# con-left-bot.net
KiCad netlist of a schematic drawn in Altium Designer
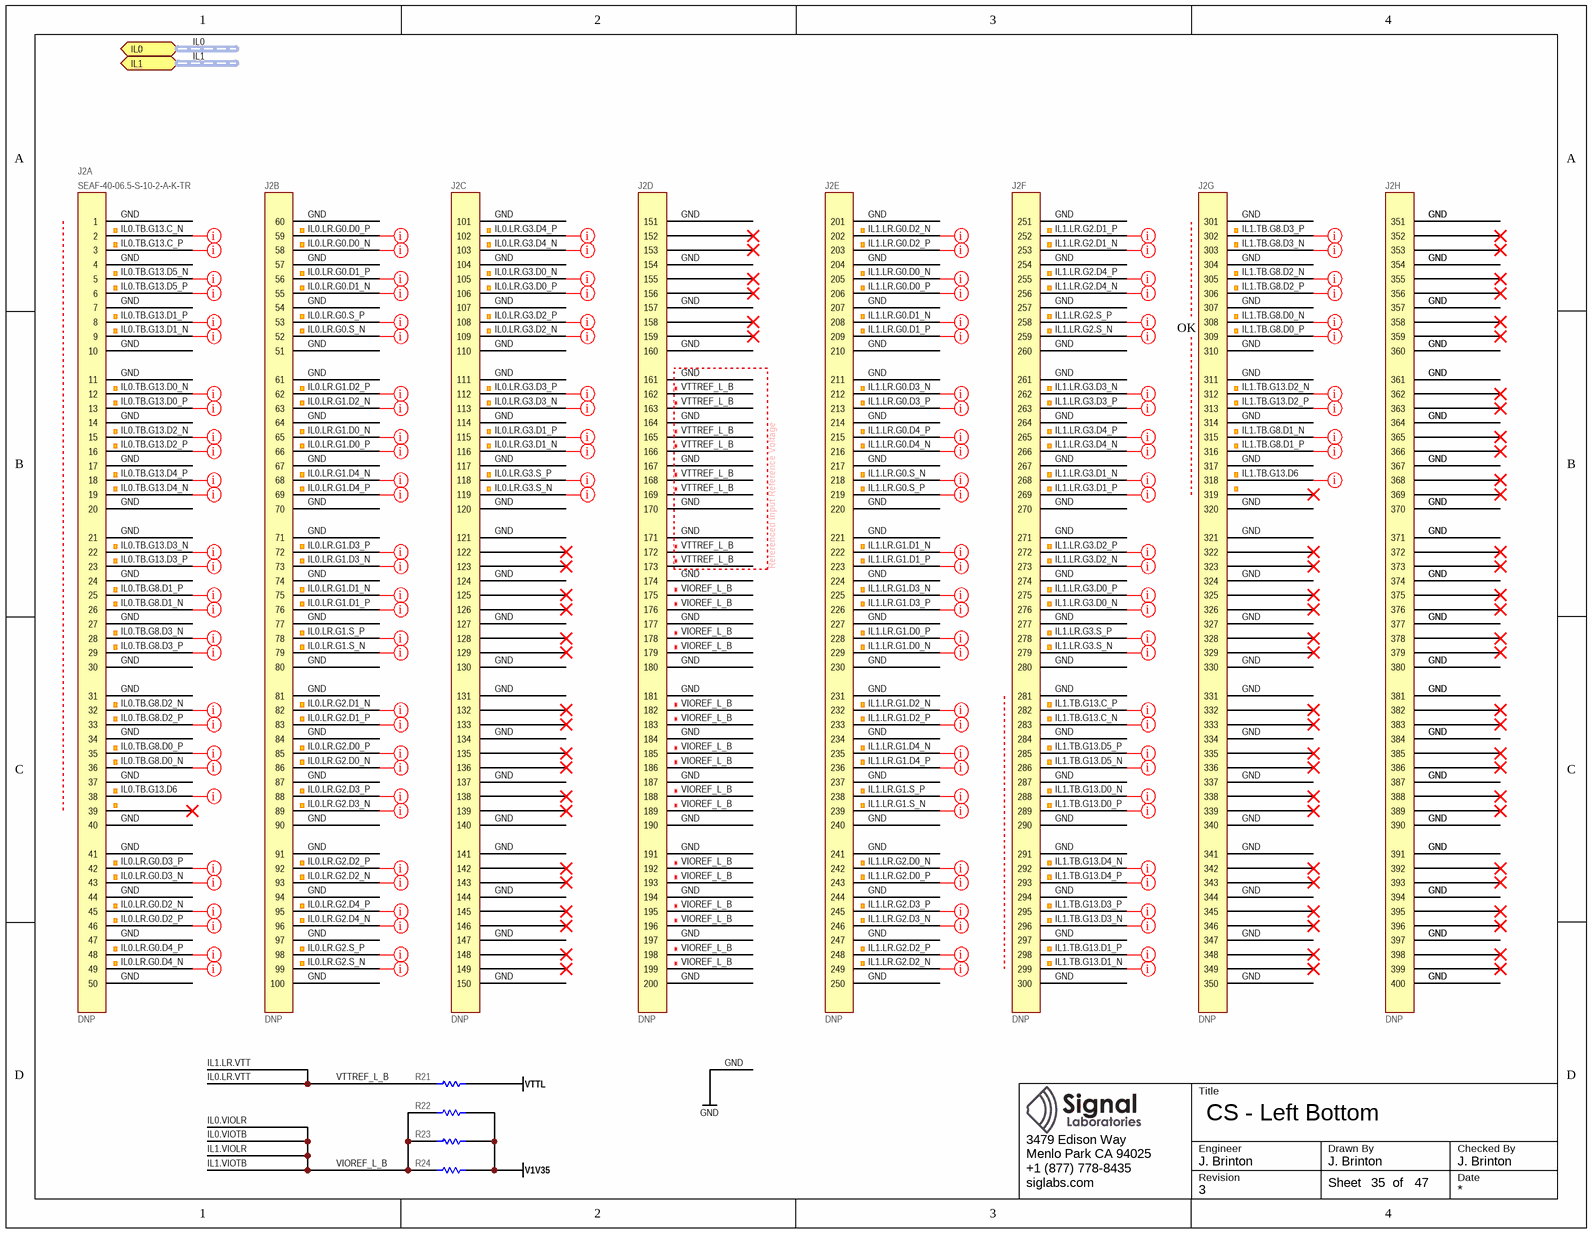
[diagram p0: con-left-bot.SchDoc]

(export (version "E")
  (design (tool "Eeschema 10.0.6"))
  (components
    (comp (ref "J2")
      (value "SEAF-40-06.5-S-10-2-A-K-TR")
      (footprint "samtec:SEAF-40-06.5-S-10-2-A-K-TR")
      (description "Terminal Array Assembly, Surface Mount, 0.050\" Pitch, 400 Pins")
      (fields (field (name "MANUFACTURER") "Samtec") (field (name "DO NOT PLACE") "DNP"))
      (libsource (lib "samtec") (part "SEAF-40-06.5-S-10-2-A-K-TR"))
    )
    (comp (ref "R21")
      (value "SOLDER_LINK")
      (footprint "SOLDERLINK0603X26N")
      (description "Solder Link")
      (libsource (lib "generic") (part "RES"))
    )
    (comp (ref "R22")
      (value "SOLDER_LINK")
      (footprint "SOLDERLINK0603X26N")
      (description "Solder Link")
      (libsource (lib "generic") (part "RES"))
    )
    (comp (ref "R23")
      (value "SOLDER_LINK")
      (footprint "SOLDERLINK0603X26N")
      (description "Solder Link")
      (libsource (lib "generic") (part "RES"))
    )
    (comp (ref "R24")
      (value "SOLDER_LINK")
      (footprint "SOLDERLINK0603X26N")
      (description "Solder Link")
      (libsource (lib "generic") (part "RES"))
    )
  )
  (nets
    (net (code "3") (name "/IL0.LR.G0.D0_N") (class "Default")
      (node (ref "J2") (pin "58") (pinfunction "58_58") (pintype "passive"))
    )
    (net (code "4") (name "/IL0.LR.G0.D0_P") (class "Default")
      (node (ref "J2") (pin "59") (pinfunction "59_59") (pintype "passive"))
    )
    (net (code "5") (name "/IL0.LR.G0.D1_N") (class "Default")
      (node (ref "J2") (pin "55") (pinfunction "55_55") (pintype "passive"))
    )
    (net (code "6") (name "/IL0.LR.G0.D1_P") (class "Default")
      (node (ref "J2") (pin "56") (pinfunction "56_56") (pintype "passive"))
    )
    (net (code "7") (name "/IL0.LR.G0.D2_N") (class "Default")
      (node (ref "J2") (pin "45") (pinfunction "45_45") (pintype "passive"))
    )
    (net (code "8") (name "/IL0.LR.G0.D2_P") (class "Default")
      (node (ref "J2") (pin "46") (pinfunction "46_46") (pintype "passive"))
    )
    (net (code "9") (name "/IL0.LR.G0.D3_N") (class "Default")
      (node (ref "J2") (pin "43") (pinfunction "43_43") (pintype "passive"))
    )
    (net (code "10") (name "/IL0.LR.G0.D3_P") (class "Default")
      (node (ref "J2") (pin "42") (pinfunction "42_42") (pintype "passive"))
    )
    (net (code "11") (name "/IL0.LR.G0.D4_N") (class "Default")
      (node (ref "J2") (pin "49") (pinfunction "49_49") (pintype "passive"))
    )
    (net (code "12") (name "/IL0.LR.G0.D4_P") (class "Default")
      (node (ref "J2") (pin "48") (pinfunction "48_48") (pintype "passive"))
    )
    (net (code "13") (name "/IL0.LR.G0.S_N") (class "Default")
      (node (ref "J2") (pin "52") (pinfunction "52_52") (pintype "passive"))
    )
    (net (code "14") (name "/IL0.LR.G0.S_P") (class "Default")
      (node (ref "J2") (pin "53") (pinfunction "53_53") (pintype "passive"))
    )
    (net (code "15") (name "/IL0.LR.G1.D0_N") (class "Default")
      (node (ref "J2") (pin "65") (pinfunction "65_65") (pintype "passive"))
    )
    (net (code "16") (name "/IL0.LR.G1.D0_P") (class "Default")
      (node (ref "J2") (pin "66") (pinfunction "66_66") (pintype "passive"))
    )
    (net (code "17") (name "/IL0.LR.G1.D1_N") (class "Default")
      (node (ref "J2") (pin "75") (pinfunction "75_75") (pintype "passive"))
    )
    (net (code "18") (name "/IL0.LR.G1.D1_P") (class "Default")
      (node (ref "J2") (pin "76") (pinfunction "76_76") (pintype "passive"))
    )
    (net (code "19") (name "/IL0.LR.G1.D2_N") (class "Default")
      (node (ref "J2") (pin "63") (pinfunction "63_63") (pintype "passive"))
    )
    (net (code "20") (name "/IL0.LR.G1.D2_P") (class "Default")
      (node (ref "J2") (pin "62") (pinfunction "62_62") (pintype "passive"))
    )
    (net (code "21") (name "/IL0.LR.G1.D3_N") (class "Default")
      (node (ref "J2") (pin "73") (pinfunction "73_73") (pintype "passive"))
    )
    (net (code "22") (name "/IL0.LR.G1.D3_P") (class "Default")
      (node (ref "J2") (pin "72") (pinfunction "72_72") (pintype "passive"))
    )
    (net (code "23") (name "/IL0.LR.G1.D4_N") (class "Default")
      (node (ref "J2") (pin "68") (pinfunction "68_68") (pintype "passive"))
    )
    (net (code "24") (name "/IL0.LR.G1.D4_P") (class "Default")
      (node (ref "J2") (pin "69") (pinfunction "69_69") (pintype "passive"))
    )
    (net (code "25") (name "/IL0.LR.G1.S_N") (class "Default")
      (node (ref "J2") (pin "79") (pinfunction "79_79") (pintype "passive"))
    )
    (net (code "26") (name "/IL0.LR.G1.S_P") (class "Default")
      (node (ref "J2") (pin "78") (pinfunction "78_78") (pintype "passive"))
    )
    (net (code "27") (name "/IL0.LR.G2.D0_N") (class "Default")
      (node (ref "J2") (pin "86") (pinfunction "86_86") (pintype "passive"))
    )
    (net (code "28") (name "/IL0.LR.G2.D0_P") (class "Default")
      (node (ref "J2") (pin "85") (pinfunction "85_85") (pintype "passive"))
    )
    (net (code "29") (name "/IL0.LR.G2.D1_N") (class "Default")
      (node (ref "J2") (pin "82") (pinfunction "82_82") (pintype "passive"))
    )
    (net (code "30") (name "/IL0.LR.G2.D1_P") (class "Default")
      (node (ref "J2") (pin "83") (pinfunction "83_83") (pintype "passive"))
    )
    (net (code "31") (name "/IL0.LR.G2.D2_N") (class "Default")
      (node (ref "J2") (pin "93") (pinfunction "93_93") (pintype "passive"))
    )
    (net (code "32") (name "/IL0.LR.G2.D2_P") (class "Default")
      (node (ref "J2") (pin "92") (pinfunction "92_92") (pintype "passive"))
    )
    (net (code "33") (name "/IL0.LR.G2.D3_N") (class "Default")
      (node (ref "J2") (pin "89") (pinfunction "89_89") (pintype "passive"))
    )
    (net (code "34") (name "/IL0.LR.G2.D3_P") (class "Default")
      (node (ref "J2") (pin "88") (pinfunction "88_88") (pintype "passive"))
    )
    (net (code "35") (name "/IL0.LR.G2.D4_N") (class "Default")
      (node (ref "J2") (pin "96") (pinfunction "96_96") (pintype "passive"))
    )
    (net (code "36") (name "/IL0.LR.G2.D4_P") (class "Default")
      (node (ref "J2") (pin "95") (pinfunction "95_95") (pintype "passive"))
    )
    (net (code "37") (name "/IL0.LR.G2.S_N") (class "Default")
      (node (ref "J2") (pin "99") (pinfunction "99_99") (pintype "passive"))
    )
    (net (code "38") (name "/IL0.LR.G2.S_P") (class "Default")
      (node (ref "J2") (pin "98") (pinfunction "98_98") (pintype "passive"))
    )
    (net (code "39") (name "/IL0.LR.G3.D0_N") (class "Default")
      (node (ref "J2") (pin "105") (pinfunction "105_105") (pintype "passive"))
    )
    (net (code "40") (name "/IL0.LR.G3.D0_P") (class "Default")
      (node (ref "J2") (pin "106") (pinfunction "106_106") (pintype "passive"))
    )
    (net (code "41") (name "/IL0.LR.G3.D1_N") (class "Default")
      (node (ref "J2") (pin "116") (pinfunction "116_116") (pintype "passive"))
    )
    (net (code "42") (name "/IL0.LR.G3.D1_P") (class "Default")
      (node (ref "J2") (pin "115") (pinfunction "115_115") (pintype "passive"))
    )
    (net (code "43") (name "/IL0.LR.G3.D2_N") (class "Default")
      (node (ref "J2") (pin "109") (pinfunction "109_109") (pintype "passive"))
    )
    (net (code "44") (name "/IL0.LR.G3.D2_P") (class "Default")
      (node (ref "J2") (pin "108") (pinfunction "108_108") (pintype "passive"))
    )
    (net (code "45") (name "/IL0.LR.G3.D3_N") (class "Default")
      (node (ref "J2") (pin "113") (pinfunction "113_113") (pintype "passive"))
    )
    (net (code "46") (name "/IL0.LR.G3.D3_P") (class "Default")
      (node (ref "J2") (pin "112") (pinfunction "112_112") (pintype "passive"))
    )
    (net (code "47") (name "/IL0.LR.G3.D4_N") (class "Default")
      (node (ref "J2") (pin "103") (pinfunction "103_103") (pintype "passive"))
    )
    (net (code "48") (name "/IL0.LR.G3.D4_P") (class "Default")
      (node (ref "J2") (pin "102") (pinfunction "102_102") (pintype "passive"))
    )
    (net (code "49") (name "/IL0.LR.G3.S_N") (class "Default")
      (node (ref "J2") (pin "119") (pinfunction "119_119") (pintype "passive"))
    )
    (net (code "50") (name "/IL0.LR.G3.S_P") (class "Default")
      (node (ref "J2") (pin "118") (pinfunction "118_118") (pintype "passive"))
    )
    (net (code "51") (name "/IL0.LR.VTT") (class "Default")
      (node (ref "J2") (pin "162") (pinfunction "162_162") (pintype "passive"))
      (node (ref "J2") (pin "163") (pinfunction "163_163") (pintype "passive"))
      (node (ref "J2") (pin "165") (pinfunction "165_165") (pintype "passive"))
      (node (ref "J2") (pin "166") (pinfunction "166_166") (pintype "passive"))
      (node (ref "J2") (pin "168") (pinfunction "168_168") (pintype "passive"))
      (node (ref "J2") (pin "169") (pinfunction "169_169") (pintype "passive"))
      (node (ref "J2") (pin "172") (pinfunction "172_172") (pintype "passive"))
      (node (ref "J2") (pin "173") (pinfunction "173_173") (pintype "passive"))
      (node (ref "R21") (pin "2") (pinfunction "2_2") (pintype "passive"))
    )
    (net (code "52") (name "/IL0.TB.G8.D0_N") (class "Default")
      (node (ref "J2") (pin "36") (pinfunction "36_36") (pintype "passive"))
    )
    (net (code "53") (name "/IL0.TB.G8.D0_P") (class "Default")
      (node (ref "J2") (pin "35") (pinfunction "35_35") (pintype "passive"))
    )
    (net (code "54") (name "/IL0.TB.G8.D1_N") (class "Default")
      (node (ref "J2") (pin "26") (pinfunction "26_26") (pintype "passive"))
    )
    (net (code "55") (name "/IL0.TB.G8.D1_P") (class "Default")
      (node (ref "J2") (pin "25") (pinfunction "25_25") (pintype "passive"))
    )
    (net (code "56") (name "/IL0.TB.G8.D2_N") (class "Default")
      (node (ref "J2") (pin "32") (pinfunction "32_32") (pintype "passive"))
    )
    (net (code "57") (name "/IL0.TB.G8.D2_P") (class "Default")
      (node (ref "J2") (pin "33") (pinfunction "33_33") (pintype "passive"))
    )
    (net (code "58") (name "/IL0.TB.G8.D3_N") (class "Default")
      (node (ref "J2") (pin "28") (pinfunction "28_28") (pintype "passive"))
    )
    (net (code "59") (name "/IL0.TB.G8.D3_P") (class "Default")
      (node (ref "J2") (pin "29") (pinfunction "29_29") (pintype "passive"))
    )
    (net (code "60") (name "/IL0.TB.G13.C_N") (class "Default")
      (node (ref "J2") (pin "2") (pinfunction "2_2") (pintype "passive"))
    )
    (net (code "61") (name "/IL0.TB.G13.C_P") (class "Default")
      (node (ref "J2") (pin "3") (pinfunction "3_3") (pintype "passive"))
    )
    (net (code "62") (name "/IL0.TB.G13.D0_N") (class "Default")
      (node (ref "J2") (pin "12") (pinfunction "12_12") (pintype "passive"))
    )
    (net (code "63") (name "/IL0.TB.G13.D0_P") (class "Default")
      (node (ref "J2") (pin "13") (pinfunction "13_13") (pintype "passive"))
    )
    (net (code "64") (name "/IL0.TB.G13.D1_N") (class "Default")
      (node (ref "J2") (pin "9") (pinfunction "9_9") (pintype "passive"))
    )
    (net (code "65") (name "/IL0.TB.G13.D1_P") (class "Default")
      (node (ref "J2") (pin "8") (pinfunction "8_8") (pintype "passive"))
    )
    (net (code "66") (name "/IL0.TB.G13.D2_N") (class "Default")
      (node (ref "J2") (pin "15") (pinfunction "15_15") (pintype "passive"))
    )
    (net (code "67") (name "/IL0.TB.G13.D2_P") (class "Default")
      (node (ref "J2") (pin "16") (pinfunction "16_16") (pintype "passive"))
    )
    (net (code "68") (name "/IL0.TB.G13.D3_N") (class "Default")
      (node (ref "J2") (pin "22") (pinfunction "22_22") (pintype "passive"))
    )
    (net (code "69") (name "/IL0.TB.G13.D3_P") (class "Default")
      (node (ref "J2") (pin "23") (pinfunction "23_23") (pintype "passive"))
    )
    (net (code "70") (name "/IL0.TB.G13.D4_N") (class "Default")
      (node (ref "J2") (pin "19") (pinfunction "19_19") (pintype "passive"))
    )
    (net (code "71") (name "/IL0.TB.G13.D4_P") (class "Default")
      (node (ref "J2") (pin "18") (pinfunction "18_18") (pintype "passive"))
    )
    (net (code "72") (name "/IL0.TB.G13.D5_N") (class "Default")
      (node (ref "J2") (pin "5") (pinfunction "5_5") (pintype "passive"))
    )
    (net (code "73") (name "/IL0.TB.G13.D5_P") (class "Default")
      (node (ref "J2") (pin "6") (pinfunction "6_6") (pintype "passive"))
    )
    (net (code "74") (name "/IL0.TB.G13.D6") (class "Default")
      (node (ref "J2") (pin "38") (pinfunction "38_38") (pintype "passive"))
    )
    (net (code "75") (name "/IL0.VIOLR") (class "Default")
      (node (ref "J2") (pin "175") (pinfunction "175_175") (pintype "passive"))
      (node (ref "J2") (pin "176") (pinfunction "176_176") (pintype "passive"))
      (node (ref "J2") (pin "178") (pinfunction "178_178") (pintype "passive"))
      (node (ref "J2") (pin "179") (pinfunction "179_179") (pintype "passive"))
      (node (ref "J2") (pin "182") (pinfunction "182_182") (pintype "passive"))
      (node (ref "J2") (pin "183") (pinfunction "183_183") (pintype "passive"))
      (node (ref "J2") (pin "185") (pinfunction "185_185") (pintype "passive"))
      (node (ref "J2") (pin "186") (pinfunction "186_186") (pintype "passive"))
      (node (ref "J2") (pin "188") (pinfunction "188_188") (pintype "passive"))
      (node (ref "J2") (pin "189") (pinfunction "189_189") (pintype "passive"))
      (node (ref "J2") (pin "192") (pinfunction "192_192") (pintype "passive"))
      (node (ref "J2") (pin "193") (pinfunction "193_193") (pintype "passive"))
      (node (ref "J2") (pin "195") (pinfunction "195_195") (pintype "passive"))
      (node (ref "J2") (pin "196") (pinfunction "196_196") (pintype "passive"))
      (node (ref "J2") (pin "198") (pinfunction "198_198") (pintype "passive"))
      (node (ref "J2") (pin "199") (pinfunction "199_199") (pintype "passive"))
      (node (ref "R22") (pin "2") (pinfunction "2_2") (pintype "passive"))
      (node (ref "R23") (pin "2") (pinfunction "2_2") (pintype "passive"))
      (node (ref "R24") (pin "2") (pinfunction "2_2") (pintype "passive"))
    )
    (net (code "76") (name "/IL1.LR.G0.D0_N") (class "Default")
      (node (ref "J2") (pin "205") (pinfunction "205_205") (pintype "passive"))
    )
    (net (code "77") (name "/IL1.LR.G0.D0_P") (class "Default")
      (node (ref "J2") (pin "206") (pinfunction "206_206") (pintype "passive"))
    )
    (net (code "78") (name "/IL1.LR.G0.D1_N") (class "Default")
      (node (ref "J2") (pin "208") (pinfunction "208_208") (pintype "passive"))
    )
    (net (code "79") (name "/IL1.LR.G0.D1_P") (class "Default")
      (node (ref "J2") (pin "209") (pinfunction "209_209") (pintype "passive"))
    )
    (net (code "80") (name "/IL1.LR.G0.D2_N") (class "Default")
      (node (ref "J2") (pin "202") (pinfunction "202_202") (pintype "passive"))
    )
    (net (code "81") (name "/IL1.LR.G0.D2_P") (class "Default")
      (node (ref "J2") (pin "203") (pinfunction "203_203") (pintype "passive"))
    )
    (net (code "82") (name "/IL1.LR.G0.D3_N") (class "Default")
      (node (ref "J2") (pin "212") (pinfunction "212_212") (pintype "passive"))
    )
    (net (code "83") (name "/IL1.LR.G0.D3_P") (class "Default")
      (node (ref "J2") (pin "213") (pinfunction "213_213") (pintype "passive"))
    )
    (net (code "84") (name "/IL1.LR.G0.D4_N") (class "Default")
      (node (ref "J2") (pin "216") (pinfunction "216_216") (pintype "passive"))
    )
    (net (code "85") (name "/IL1.LR.G0.D4_P") (class "Default")
      (node (ref "J2") (pin "215") (pinfunction "215_215") (pintype "passive"))
    )
    (net (code "86") (name "/IL1.LR.G0.S_N") (class "Default")
      (node (ref "J2") (pin "218") (pinfunction "218_218") (pintype "passive"))
    )
    (net (code "87") (name "/IL1.LR.G0.S_P") (class "Default")
      (node (ref "J2") (pin "219") (pinfunction "219_219") (pintype "passive"))
    )
    (net (code "88") (name "/IL1.LR.G1.D0_N") (class "Default")
      (node (ref "J2") (pin "229") (pinfunction "229_229") (pintype "passive"))
    )
    (net (code "89") (name "/IL1.LR.G1.D0_P") (class "Default")
      (node (ref "J2") (pin "228") (pinfunction "228_228") (pintype "passive"))
    )
    (net (code "90") (name "/IL1.LR.G1.D1_N") (class "Default")
      (node (ref "J2") (pin "222") (pinfunction "222_222") (pintype "passive"))
    )
    (net (code "91") (name "/IL1.LR.G1.D1_P") (class "Default")
      (node (ref "J2") (pin "223") (pinfunction "223_223") (pintype "passive"))
    )
    (net (code "92") (name "/IL1.LR.G1.D2_N") (class "Default")
      (node (ref "J2") (pin "232") (pinfunction "232_232") (pintype "passive"))
    )
    (net (code "93") (name "/IL1.LR.G1.D2_P") (class "Default")
      (node (ref "J2") (pin "233") (pinfunction "233_233") (pintype "passive"))
    )
    (net (code "94") (name "/IL1.LR.G1.D3_N") (class "Default")
      (node (ref "J2") (pin "225") (pinfunction "225_225") (pintype "passive"))
    )
    (net (code "95") (name "/IL1.LR.G1.D3_P") (class "Default")
      (node (ref "J2") (pin "226") (pinfunction "226_226") (pintype "passive"))
    )
    (net (code "96") (name "/IL1.LR.G1.D4_N") (class "Default")
      (node (ref "J2") (pin "235") (pinfunction "235_235") (pintype "passive"))
    )
    (net (code "97") (name "/IL1.LR.G1.D4_P") (class "Default")
      (node (ref "J2") (pin "236") (pinfunction "236_236") (pintype "passive"))
    )
    (net (code "98") (name "/IL1.LR.G1.S_N") (class "Default")
      (node (ref "J2") (pin "239") (pinfunction "239_239") (pintype "passive"))
    )
    (net (code "99") (name "/IL1.LR.G1.S_P") (class "Default")
      (node (ref "J2") (pin "238") (pinfunction "238_238") (pintype "passive"))
    )
    (net (code "100") (name "/IL1.LR.G2.D0_N") (class "Default")
      (node (ref "J2") (pin "242") (pinfunction "242_242") (pintype "passive"))
    )
    (net (code "101") (name "/IL1.LR.G2.D0_P") (class "Default")
      (node (ref "J2") (pin "243") (pinfunction "243_243") (pintype "passive"))
    )
    (net (code "102") (name "/IL1.LR.G2.D1_N") (class "Default")
      (node (ref "J2") (pin "253") (pinfunction "253_253") (pintype "passive"))
    )
    (net (code "103") (name "/IL1.LR.G2.D1_P") (class "Default")
      (node (ref "J2") (pin "252") (pinfunction "252_252") (pintype "passive"))
    )
    (net (code "104") (name "/IL1.LR.G2.D2_N") (class "Default")
      (node (ref "J2") (pin "249") (pinfunction "249_249") (pintype "passive"))
    )
    (net (code "105") (name "/IL1.LR.G2.D2_P") (class "Default")
      (node (ref "J2") (pin "248") (pinfunction "248_248") (pintype "passive"))
    )
    (net (code "106") (name "/IL1.LR.G2.D3_N") (class "Default")
      (node (ref "J2") (pin "246") (pinfunction "246_246") (pintype "passive"))
    )
    (net (code "107") (name "/IL1.LR.G2.D3_P") (class "Default")
      (node (ref "J2") (pin "245") (pinfunction "245_245") (pintype "passive"))
    )
    (net (code "108") (name "/IL1.LR.G2.D4_N") (class "Default")
      (node (ref "J2") (pin "256") (pinfunction "256_256") (pintype "passive"))
    )
    (net (code "109") (name "/IL1.LR.G2.D4_P") (class "Default")
      (node (ref "J2") (pin "255") (pinfunction "255_255") (pintype "passive"))
    )
    (net (code "110") (name "/IL1.LR.G2.S_N") (class "Default")
      (node (ref "J2") (pin "259") (pinfunction "259_259") (pintype "passive"))
    )
    (net (code "111") (name "/IL1.LR.G2.S_P") (class "Default")
      (node (ref "J2") (pin "258") (pinfunction "258_258") (pintype "passive"))
    )
    (net (code "112") (name "/IL1.LR.G3.D0_N") (class "Default")
      (node (ref "J2") (pin "276") (pinfunction "276_276") (pintype "passive"))
    )
    (net (code "113") (name "/IL1.LR.G3.D0_P") (class "Default")
      (node (ref "J2") (pin "275") (pinfunction "275_275") (pintype "passive"))
    )
    (net (code "114") (name "/IL1.LR.G3.D1_N") (class "Default")
      (node (ref "J2") (pin "268") (pinfunction "268_268") (pintype "passive"))
    )
    (net (code "115") (name "/IL1.LR.G3.D1_P") (class "Default")
      (node (ref "J2") (pin "269") (pinfunction "269_269") (pintype "passive"))
    )
    (net (code "116") (name "/IL1.LR.G3.D2_N") (class "Default")
      (node (ref "J2") (pin "273") (pinfunction "273_273") (pintype "passive"))
    )
    (net (code "117") (name "/IL1.LR.G3.D2_P") (class "Default")
      (node (ref "J2") (pin "272") (pinfunction "272_272") (pintype "passive"))
    )
    (net (code "118") (name "/IL1.LR.G3.D3_N") (class "Default")
      (node (ref "J2") (pin "262") (pinfunction "262_262") (pintype "passive"))
    )
    (net (code "119") (name "/IL1.LR.G3.D3_P") (class "Default")
      (node (ref "J2") (pin "263") (pinfunction "263_263") (pintype "passive"))
    )
    (net (code "120") (name "/IL1.LR.G3.D4_N") (class "Default")
      (node (ref "J2") (pin "266") (pinfunction "266_266") (pintype "passive"))
    )
    (net (code "121") (name "/IL1.LR.G3.D4_P") (class "Default")
      (node (ref "J2") (pin "265") (pinfunction "265_265") (pintype "passive"))
    )
    (net (code "122") (name "/IL1.LR.G3.S_N") (class "Default")
      (node (ref "J2") (pin "279") (pinfunction "279_279") (pintype "passive"))
    )
    (net (code "123") (name "/IL1.LR.G3.S_P") (class "Default")
      (node (ref "J2") (pin "278") (pinfunction "278_278") (pintype "passive"))
    )
    (net (code "124") (name "/IL1.TB.G8.D0_N") (class "Default")
      (node (ref "J2") (pin "308") (pinfunction "308_308") (pintype "passive"))
    )
    (net (code "125") (name "/IL1.TB.G8.D0_P") (class "Default")
      (node (ref "J2") (pin "309") (pinfunction "309_309") (pintype "passive"))
    )
    (net (code "126") (name "/IL1.TB.G8.D1_N") (class "Default")
      (node (ref "J2") (pin "315") (pinfunction "315_315") (pintype "passive"))
    )
    (net (code "127") (name "/IL1.TB.G8.D1_P") (class "Default")
      (node (ref "J2") (pin "316") (pinfunction "316_316") (pintype "passive"))
    )
    (net (code "128") (name "/IL1.TB.G8.D2_N") (class "Default")
      (node (ref "J2") (pin "305") (pinfunction "305_305") (pintype "passive"))
    )
    (net (code "129") (name "/IL1.TB.G8.D2_P") (class "Default")
      (node (ref "J2") (pin "306") (pinfunction "306_306") (pintype "passive"))
    )
    (net (code "130") (name "/IL1.TB.G8.D3_N") (class "Default")
      (node (ref "J2") (pin "303") (pinfunction "303_303") (pintype "passive"))
    )
    (net (code "131") (name "/IL1.TB.G8.D3_P") (class "Default")
      (node (ref "J2") (pin "302") (pinfunction "302_302") (pintype "passive"))
    )
    (net (code "132") (name "/IL1.TB.G13.C_N") (class "Default")
      (node (ref "J2") (pin "283") (pinfunction "283_283") (pintype "passive"))
    )
    (net (code "133") (name "/IL1.TB.G13.C_P") (class "Default")
      (node (ref "J2") (pin "282") (pinfunction "282_282") (pintype "passive"))
    )
    (net (code "134") (name "/IL1.TB.G13.D0_N") (class "Default")
      (node (ref "J2") (pin "288") (pinfunction "288_288") (pintype "passive"))
    )
    (net (code "135") (name "/IL1.TB.G13.D0_P") (class "Default")
      (node (ref "J2") (pin "289") (pinfunction "289_289") (pintype "passive"))
    )
    (net (code "136") (name "/IL1.TB.G13.D1_N") (class "Default")
      (node (ref "J2") (pin "299") (pinfunction "299_299") (pintype "passive"))
    )
    (net (code "137") (name "/IL1.TB.G13.D1_P") (class "Default")
      (node (ref "J2") (pin "298") (pinfunction "298_298") (pintype "passive"))
    )
    (net (code "138") (name "/IL1.TB.G13.D2_N") (class "Default")
      (node (ref "J2") (pin "312") (pinfunction "312_312") (pintype "passive"))
    )
    (net (code "139") (name "/IL1.TB.G13.D2_P") (class "Default")
      (node (ref "J2") (pin "313") (pinfunction "313_313") (pintype "passive"))
    )
    (net (code "140") (name "/IL1.TB.G13.D3_N") (class "Default")
      (node (ref "J2") (pin "296") (pinfunction "296_296") (pintype "passive"))
    )
    (net (code "141") (name "/IL1.TB.G13.D3_P") (class "Default")
      (node (ref "J2") (pin "295") (pinfunction "295_295") (pintype "passive"))
    )
    (net (code "142") (name "/IL1.TB.G13.D4_N") (class "Default")
      (node (ref "J2") (pin "292") (pinfunction "292_292") (pintype "passive"))
    )
    (net (code "143") (name "/IL1.TB.G13.D4_P") (class "Default")
      (node (ref "J2") (pin "293") (pinfunction "293_293") (pintype "passive"))
    )
    (net (code "144") (name "/IL1.TB.G13.D5_N") (class "Default")
      (node (ref "J2") (pin "286") (pinfunction "286_286") (pintype "passive"))
    )
    (net (code "145") (name "/IL1.TB.G13.D5_P") (class "Default")
      (node (ref "J2") (pin "285") (pinfunction "285_285") (pintype "passive"))
    )
    (net (code "146") (name "/IL1.TB.G13.D6") (class "Default")
      (node (ref "J2") (pin "318") (pinfunction "318_318") (pintype "passive"))
    )
    (net (code "149") (name "GND") (class "Default")
      (node (ref "J2") (pin "1") (pinfunction "1_1") (pintype "passive"))
      (node (ref "J2") (pin "10") (pinfunction "10_10") (pintype "passive"))
      (node (ref "J2") (pin "100") (pinfunction "100_100") (pintype "passive"))
      (node (ref "J2") (pin "101") (pinfunction "101_101") (pintype "passive"))
      (node (ref "J2") (pin "104") (pinfunction "104_104") (pintype "passive"))
      (node (ref "J2") (pin "107") (pinfunction "107_107") (pintype "passive"))
      (node (ref "J2") (pin "11") (pinfunction "11_11") (pintype "passive"))
      (node (ref "J2") (pin "110") (pinfunction "110_110") (pintype "passive"))
      (node (ref "J2") (pin "111") (pinfunction "111_111") (pintype "passive"))
      (node (ref "J2") (pin "114") (pinfunction "114_114") (pintype "passive"))
      (node (ref "J2") (pin "117") (pinfunction "117_117") (pintype "passive"))
      (node (ref "J2") (pin "120") (pinfunction "120_120") (pintype "passive"))
      (node (ref "J2") (pin "121") (pinfunction "121_121") (pintype "passive"))
      (node (ref "J2") (pin "124") (pinfunction "124_124") (pintype "passive"))
      (node (ref "J2") (pin "127") (pinfunction "127_127") (pintype "passive"))
      (node (ref "J2") (pin "130") (pinfunction "130_130") (pintype "passive"))
      (node (ref "J2") (pin "131") (pinfunction "131_131") (pintype "passive"))
      (node (ref "J2") (pin "134") (pinfunction "134_134") (pintype "passive"))
      (node (ref "J2") (pin "137") (pinfunction "137_137") (pintype "passive"))
      (node (ref "J2") (pin "14") (pinfunction "14_14") (pintype "passive"))
      (node (ref "J2") (pin "140") (pinfunction "140_140") (pintype "passive"))
      (node (ref "J2") (pin "141") (pinfunction "141_141") (pintype "passive"))
      (node (ref "J2") (pin "144") (pinfunction "144_144") (pintype "passive"))
      (node (ref "J2") (pin "147") (pinfunction "147_147") (pintype "passive"))
      (node (ref "J2") (pin "150") (pinfunction "150_150") (pintype "passive"))
      (node (ref "J2") (pin "151") (pinfunction "151_151") (pintype "passive"))
      (node (ref "J2") (pin "154") (pinfunction "154_154") (pintype "passive"))
      (node (ref "J2") (pin "157") (pinfunction "157_157") (pintype "passive"))
      (node (ref "J2") (pin "160") (pinfunction "160_160") (pintype "passive"))
      (node (ref "J2") (pin "161") (pinfunction "161_161") (pintype "passive"))
      (node (ref "J2") (pin "164") (pinfunction "164_164") (pintype "passive"))
      (node (ref "J2") (pin "167") (pinfunction "167_167") (pintype "passive"))
      (node (ref "J2") (pin "17") (pinfunction "17_17") (pintype "passive"))
      (node (ref "J2") (pin "170") (pinfunction "170_170") (pintype "passive"))
      (node (ref "J2") (pin "171") (pinfunction "171_171") (pintype "passive"))
      (node (ref "J2") (pin "174") (pinfunction "174_174") (pintype "passive"))
      (node (ref "J2") (pin "177") (pinfunction "177_177") (pintype "passive"))
      (node (ref "J2") (pin "180") (pinfunction "180_180") (pintype "passive"))
      (node (ref "J2") (pin "181") (pinfunction "181_181") (pintype "passive"))
      (node (ref "J2") (pin "184") (pinfunction "184_184") (pintype "passive"))
      (node (ref "J2") (pin "187") (pinfunction "187_187") (pintype "passive"))
      (node (ref "J2") (pin "190") (pinfunction "190_190") (pintype "passive"))
      (node (ref "J2") (pin "191") (pinfunction "191_191") (pintype "passive"))
      (node (ref "J2") (pin "194") (pinfunction "194_194") (pintype "passive"))
      (node (ref "J2") (pin "197") (pinfunction "197_197") (pintype "passive"))
      (node (ref "J2") (pin "20") (pinfunction "20_20") (pintype "passive"))
      (node (ref "J2") (pin "200") (pinfunction "200_200") (pintype "passive"))
      (node (ref "J2") (pin "201") (pinfunction "201_201") (pintype "passive"))
      (node (ref "J2") (pin "204") (pinfunction "204_204") (pintype "passive"))
      (node (ref "J2") (pin "207") (pinfunction "207_207") (pintype "passive"))
      (node (ref "J2") (pin "21") (pinfunction "21_21") (pintype "passive"))
      (node (ref "J2") (pin "210") (pinfunction "210_210") (pintype "passive"))
      (node (ref "J2") (pin "211") (pinfunction "211_211") (pintype "passive"))
      (node (ref "J2") (pin "214") (pinfunction "214_214") (pintype "passive"))
      (node (ref "J2") (pin "217") (pinfunction "217_217") (pintype "passive"))
      (node (ref "J2") (pin "220") (pinfunction "220_220") (pintype "passive"))
      (node (ref "J2") (pin "221") (pinfunction "221_221") (pintype "passive"))
      (node (ref "J2") (pin "224") (pinfunction "224_224") (pintype "passive"))
      (node (ref "J2") (pin "227") (pinfunction "227_227") (pintype "passive"))
      (node (ref "J2") (pin "230") (pinfunction "230_230") (pintype "passive"))
      (node (ref "J2") (pin "231") (pinfunction "231_231") (pintype "passive"))
      (node (ref "J2") (pin "234") (pinfunction "234_234") (pintype "passive"))
      (node (ref "J2") (pin "237") (pinfunction "237_237") (pintype "passive"))
      (node (ref "J2") (pin "24") (pinfunction "24_24") (pintype "passive"))
      (node (ref "J2") (pin "240") (pinfunction "240_240") (pintype "passive"))
      (node (ref "J2") (pin "241") (pinfunction "241_241") (pintype "passive"))
      (node (ref "J2") (pin "244") (pinfunction "244_244") (pintype "passive"))
      (node (ref "J2") (pin "247") (pinfunction "247_247") (pintype "passive"))
      (node (ref "J2") (pin "250") (pinfunction "250_250") (pintype "passive"))
      (node (ref "J2") (pin "251") (pinfunction "251_251") (pintype "passive"))
      (node (ref "J2") (pin "254") (pinfunction "254_254") (pintype "passive"))
      (node (ref "J2") (pin "257") (pinfunction "257_257") (pintype "passive"))
      (node (ref "J2") (pin "260") (pinfunction "260_260") (pintype "passive"))
      (node (ref "J2") (pin "261") (pinfunction "261_261") (pintype "passive"))
      (node (ref "J2") (pin "264") (pinfunction "264_264") (pintype "passive"))
      (node (ref "J2") (pin "267") (pinfunction "267_267") (pintype "passive"))
      (node (ref "J2") (pin "27") (pinfunction "27_27") (pintype "passive"))
      (node (ref "J2") (pin "270") (pinfunction "270_270") (pintype "passive"))
      (node (ref "J2") (pin "271") (pinfunction "271_271") (pintype "passive"))
      (node (ref "J2") (pin "274") (pinfunction "274_274") (pintype "passive"))
      (node (ref "J2") (pin "277") (pinfunction "277_277") (pintype "passive"))
      (node (ref "J2") (pin "280") (pinfunction "280_280") (pintype "passive"))
      (node (ref "J2") (pin "281") (pinfunction "281_281") (pintype "passive"))
      (node (ref "J2") (pin "284") (pinfunction "284_284") (pintype "passive"))
      (node (ref "J2") (pin "287") (pinfunction "287_287") (pintype "passive"))
      (node (ref "J2") (pin "290") (pinfunction "290_290") (pintype "passive"))
      (node (ref "J2") (pin "291") (pinfunction "291_291") (pintype "passive"))
      (node (ref "J2") (pin "294") (pinfunction "294_294") (pintype "passive"))
      (node (ref "J2") (pin "297") (pinfunction "297_297") (pintype "passive"))
      (node (ref "J2") (pin "30") (pinfunction "30_30") (pintype "passive"))
      (node (ref "J2") (pin "300") (pinfunction "300_300") (pintype "passive"))
      (node (ref "J2") (pin "301") (pinfunction "301_301") (pintype "passive"))
      (node (ref "J2") (pin "304") (pinfunction "304_304") (pintype "passive"))
      (node (ref "J2") (pin "307") (pinfunction "307_307") (pintype "passive"))
      (node (ref "J2") (pin "31") (pinfunction "31_31") (pintype "passive"))
      (node (ref "J2") (pin "310") (pinfunction "310_310") (pintype "passive"))
      (node (ref "J2") (pin "311") (pinfunction "311_311") (pintype "passive"))
      (node (ref "J2") (pin "314") (pinfunction "314_314") (pintype "passive"))
      (node (ref "J2") (pin "317") (pinfunction "317_317") (pintype "passive"))
      (node (ref "J2") (pin "320") (pinfunction "320_320") (pintype "passive"))
      (node (ref "J2") (pin "321") (pinfunction "321_321") (pintype "passive"))
      (node (ref "J2") (pin "324") (pinfunction "324_324") (pintype "passive"))
      (node (ref "J2") (pin "327") (pinfunction "327_327") (pintype "passive"))
      (node (ref "J2") (pin "330") (pinfunction "330_330") (pintype "passive"))
      (node (ref "J2") (pin "331") (pinfunction "331_331") (pintype "passive"))
      (node (ref "J2") (pin "334") (pinfunction "334_334") (pintype "passive"))
      (node (ref "J2") (pin "337") (pinfunction "337_337") (pintype "passive"))
      (node (ref "J2") (pin "34") (pinfunction "34_34") (pintype "passive"))
      (node (ref "J2") (pin "340") (pinfunction "340_340") (pintype "passive"))
      (node (ref "J2") (pin "341") (pinfunction "341_341") (pintype "passive"))
      (node (ref "J2") (pin "344") (pinfunction "344_344") (pintype "passive"))
      (node (ref "J2") (pin "347") (pinfunction "347_347") (pintype "passive"))
      (node (ref "J2") (pin "350") (pinfunction "350_350") (pintype "passive"))
      (node (ref "J2") (pin "351") (pinfunction "351_351") (pintype "passive"))
      (node (ref "J2") (pin "354") (pinfunction "354_354") (pintype "passive"))
      (node (ref "J2") (pin "357") (pinfunction "357_357") (pintype "passive"))
      (node (ref "J2") (pin "360") (pinfunction "360_360") (pintype "passive"))
      (node (ref "J2") (pin "361") (pinfunction "361_361") (pintype "passive"))
      (node (ref "J2") (pin "364") (pinfunction "364_364") (pintype "passive"))
      (node (ref "J2") (pin "367") (pinfunction "367_367") (pintype "passive"))
      (node (ref "J2") (pin "37") (pinfunction "37_37") (pintype "passive"))
      (node (ref "J2") (pin "370") (pinfunction "370_370") (pintype "passive"))
      (node (ref "J2") (pin "371") (pinfunction "371_371") (pintype "passive"))
      (node (ref "J2") (pin "374") (pinfunction "374_374") (pintype "passive"))
      (node (ref "J2") (pin "377") (pinfunction "377_377") (pintype "passive"))
      (node (ref "J2") (pin "380") (pinfunction "380_380") (pintype "passive"))
      (node (ref "J2") (pin "381") (pinfunction "381_381") (pintype "passive"))
      (node (ref "J2") (pin "384") (pinfunction "384_384") (pintype "passive"))
      (node (ref "J2") (pin "387") (pinfunction "387_387") (pintype "passive"))
      (node (ref "J2") (pin "390") (pinfunction "390_390") (pintype "passive"))
      (node (ref "J2") (pin "391") (pinfunction "391_391") (pintype "passive"))
      (node (ref "J2") (pin "394") (pinfunction "394_394") (pintype "passive"))
      (node (ref "J2") (pin "397") (pinfunction "397_397") (pintype "passive"))
      (node (ref "J2") (pin "4") (pinfunction "4_4") (pintype "passive"))
      (node (ref "J2") (pin "40") (pinfunction "40_40") (pintype "passive"))
      (node (ref "J2") (pin "400") (pinfunction "400_400") (pintype "passive"))
      (node (ref "J2") (pin "41") (pinfunction "41_41") (pintype "passive"))
      (node (ref "J2") (pin "44") (pinfunction "44_44") (pintype "passive"))
      (node (ref "J2") (pin "47") (pinfunction "47_47") (pintype "passive"))
      (node (ref "J2") (pin "50") (pinfunction "50_50") (pintype "passive"))
      (node (ref "J2") (pin "51") (pinfunction "51_51") (pintype "passive"))
      (node (ref "J2") (pin "54") (pinfunction "54_54") (pintype "passive"))
      (node (ref "J2") (pin "57") (pinfunction "57_57") (pintype "passive"))
      (node (ref "J2") (pin "60") (pinfunction "60_60") (pintype "passive"))
      (node (ref "J2") (pin "61") (pinfunction "61_61") (pintype "passive"))
      (node (ref "J2") (pin "64") (pinfunction "64_64") (pintype "passive"))
      (node (ref "J2") (pin "67") (pinfunction "67_67") (pintype "passive"))
      (node (ref "J2") (pin "7") (pinfunction "7_7") (pintype "passive"))
      (node (ref "J2") (pin "70") (pinfunction "70_70") (pintype "passive"))
      (node (ref "J2") (pin "71") (pinfunction "71_71") (pintype "passive"))
      (node (ref "J2") (pin "74") (pinfunction "74_74") (pintype "passive"))
      (node (ref "J2") (pin "77") (pinfunction "77_77") (pintype "passive"))
      (node (ref "J2") (pin "80") (pinfunction "80_80") (pintype "passive"))
      (node (ref "J2") (pin "81") (pinfunction "81_81") (pintype "passive"))
      (node (ref "J2") (pin "84") (pinfunction "84_84") (pintype "passive"))
      (node (ref "J2") (pin "87") (pinfunction "87_87") (pintype "passive"))
      (node (ref "J2") (pin "90") (pinfunction "90_90") (pintype "passive"))
      (node (ref "J2") (pin "91") (pinfunction "91_91") (pintype "passive"))
      (node (ref "J2") (pin "94") (pinfunction "94_94") (pintype "passive"))
      (node (ref "J2") (pin "97") (pinfunction "97_97") (pintype "passive"))
    )
    (net (code "150") (name "V1V35") (class "Default")
      (node (ref "R22") (pin "1") (pinfunction "1_1") (pintype "passive"))
      (node (ref "R23") (pin "1") (pinfunction "1_1") (pintype "passive"))
      (node (ref "R24") (pin "1") (pinfunction "1_1") (pintype "passive"))
    )
    (net (code "151") (name "VTTL") (class "Default")
      (node (ref "R21") (pin "1") (pinfunction "1_1") (pintype "passive"))
    )
    (net (code "152") (name "unconnected-(J2-Pad39)") (class "Default")
      (node (ref "J2") (pin "39") (pinfunction "39_39") (pintype "passive+no_connect"))
    )
    (net (code "153") (name "unconnected-(J2-Pad122)") (class "Default")
      (node (ref "J2") (pin "122") (pinfunction "122_122") (pintype "passive+no_connect"))
    )
    (net (code "154") (name "unconnected-(J2-Pad123)") (class "Default")
      (node (ref "J2") (pin "123") (pinfunction "123_123") (pintype "passive+no_connect"))
    )
    (net (code "155") (name "unconnected-(J2-Pad125)") (class "Default")
      (node (ref "J2") (pin "125") (pinfunction "125_125") (pintype "passive+no_connect"))
    )
    (net (code "156") (name "unconnected-(J2-Pad126)") (class "Default")
      (node (ref "J2") (pin "126") (pinfunction "126_126") (pintype "passive+no_connect"))
    )
    (net (code "157") (name "unconnected-(J2-Pad128)") (class "Default")
      (node (ref "J2") (pin "128") (pinfunction "128_128") (pintype "passive+no_connect"))
    )
    (net (code "158") (name "unconnected-(J2-Pad129)") (class "Default")
      (node (ref "J2") (pin "129") (pinfunction "129_129") (pintype "passive+no_connect"))
    )
    (net (code "159") (name "unconnected-(J2-Pad132)") (class "Default")
      (node (ref "J2") (pin "132") (pinfunction "132_132") (pintype "passive+no_connect"))
    )
    (net (code "160") (name "unconnected-(J2-Pad133)") (class "Default")
      (node (ref "J2") (pin "133") (pinfunction "133_133") (pintype "passive+no_connect"))
    )
    (net (code "161") (name "unconnected-(J2-Pad135)") (class "Default")
      (node (ref "J2") (pin "135") (pinfunction "135_135") (pintype "passive+no_connect"))
    )
    (net (code "162") (name "unconnected-(J2-Pad136)") (class "Default")
      (node (ref "J2") (pin "136") (pinfunction "136_136") (pintype "passive+no_connect"))
    )
    (net (code "163") (name "unconnected-(J2-Pad138)") (class "Default")
      (node (ref "J2") (pin "138") (pinfunction "138_138") (pintype "passive+no_connect"))
    )
    (net (code "164") (name "unconnected-(J2-Pad139)") (class "Default")
      (node (ref "J2") (pin "139") (pinfunction "139_139") (pintype "passive+no_connect"))
    )
    (net (code "165") (name "unconnected-(J2-Pad142)") (class "Default")
      (node (ref "J2") (pin "142") (pinfunction "142_142") (pintype "passive+no_connect"))
    )
    (net (code "166") (name "unconnected-(J2-Pad143)") (class "Default")
      (node (ref "J2") (pin "143") (pinfunction "143_143") (pintype "passive+no_connect"))
    )
    (net (code "167") (name "unconnected-(J2-Pad145)") (class "Default")
      (node (ref "J2") (pin "145") (pinfunction "145_145") (pintype "passive+no_connect"))
    )
    (net (code "168") (name "unconnected-(J2-Pad146)") (class "Default")
      (node (ref "J2") (pin "146") (pinfunction "146_146") (pintype "passive+no_connect"))
    )
    (net (code "169") (name "unconnected-(J2-Pad148)") (class "Default")
      (node (ref "J2") (pin "148") (pinfunction "148_148") (pintype "passive+no_connect"))
    )
    (net (code "170") (name "unconnected-(J2-Pad149)") (class "Default")
      (node (ref "J2") (pin "149") (pinfunction "149_149") (pintype "passive+no_connect"))
    )
    (net (code "171") (name "unconnected-(J2-Pad152)") (class "Default")
      (node (ref "J2") (pin "152") (pinfunction "152_152") (pintype "passive+no_connect"))
    )
    (net (code "172") (name "unconnected-(J2-Pad153)") (class "Default")
      (node (ref "J2") (pin "153") (pinfunction "153_153") (pintype "passive+no_connect"))
    )
    (net (code "173") (name "unconnected-(J2-Pad155)") (class "Default")
      (node (ref "J2") (pin "155") (pinfunction "155_155") (pintype "passive+no_connect"))
    )
    (net (code "174") (name "unconnected-(J2-Pad156)") (class "Default")
      (node (ref "J2") (pin "156") (pinfunction "156_156") (pintype "passive+no_connect"))
    )
    (net (code "175") (name "unconnected-(J2-Pad158)") (class "Default")
      (node (ref "J2") (pin "158") (pinfunction "158_158") (pintype "passive+no_connect"))
    )
    (net (code "176") (name "unconnected-(J2-Pad159)") (class "Default")
      (node (ref "J2") (pin "159") (pinfunction "159_159") (pintype "passive+no_connect"))
    )
    (net (code "177") (name "unconnected-(J2-Pad319)") (class "Default")
      (node (ref "J2") (pin "319") (pinfunction "319_319") (pintype "passive+no_connect"))
    )
    (net (code "178") (name "unconnected-(J2-Pad322)") (class "Default")
      (node (ref "J2") (pin "322") (pinfunction "322_322") (pintype "passive+no_connect"))
    )
    (net (code "179") (name "unconnected-(J2-Pad323)") (class "Default")
      (node (ref "J2") (pin "323") (pinfunction "323_323") (pintype "passive+no_connect"))
    )
    (net (code "180") (name "unconnected-(J2-Pad325)") (class "Default")
      (node (ref "J2") (pin "325") (pinfunction "325_325") (pintype "passive+no_connect"))
    )
    (net (code "181") (name "unconnected-(J2-Pad326)") (class "Default")
      (node (ref "J2") (pin "326") (pinfunction "326_326") (pintype "passive+no_connect"))
    )
    (net (code "182") (name "unconnected-(J2-Pad328)") (class "Default")
      (node (ref "J2") (pin "328") (pinfunction "328_328") (pintype "passive+no_connect"))
    )
    (net (code "183") (name "unconnected-(J2-Pad329)") (class "Default")
      (node (ref "J2") (pin "329") (pinfunction "329_329") (pintype "passive+no_connect"))
    )
    (net (code "184") (name "unconnected-(J2-Pad332)") (class "Default")
      (node (ref "J2") (pin "332") (pinfunction "332_332") (pintype "passive+no_connect"))
    )
    (net (code "185") (name "unconnected-(J2-Pad333)") (class "Default")
      (node (ref "J2") (pin "333") (pinfunction "333_333") (pintype "passive+no_connect"))
    )
    (net (code "186") (name "unconnected-(J2-Pad335)") (class "Default")
      (node (ref "J2") (pin "335") (pinfunction "335_335") (pintype "passive+no_connect"))
    )
    (net (code "187") (name "unconnected-(J2-Pad336)") (class "Default")
      (node (ref "J2") (pin "336") (pinfunction "336_336") (pintype "passive+no_connect"))
    )
    (net (code "188") (name "unconnected-(J2-Pad338)") (class "Default")
      (node (ref "J2") (pin "338") (pinfunction "338_338") (pintype "passive+no_connect"))
    )
    (net (code "189") (name "unconnected-(J2-Pad339)") (class "Default")
      (node (ref "J2") (pin "339") (pinfunction "339_339") (pintype "passive+no_connect"))
    )
    (net (code "190") (name "unconnected-(J2-Pad342)") (class "Default")
      (node (ref "J2") (pin "342") (pinfunction "342_342") (pintype "passive+no_connect"))
    )
    (net (code "191") (name "unconnected-(J2-Pad343)") (class "Default")
      (node (ref "J2") (pin "343") (pinfunction "343_343") (pintype "passive+no_connect"))
    )
    (net (code "192") (name "unconnected-(J2-Pad345)") (class "Default")
      (node (ref "J2") (pin "345") (pinfunction "345_345") (pintype "passive+no_connect"))
    )
    (net (code "193") (name "unconnected-(J2-Pad346)") (class "Default")
      (node (ref "J2") (pin "346") (pinfunction "346_346") (pintype "passive+no_connect"))
    )
    (net (code "194") (name "unconnected-(J2-Pad348)") (class "Default")
      (node (ref "J2") (pin "348") (pinfunction "348_348") (pintype "passive+no_connect"))
    )
    (net (code "195") (name "unconnected-(J2-Pad349)") (class "Default")
      (node (ref "J2") (pin "349") (pinfunction "349_349") (pintype "passive+no_connect"))
    )
    (net (code "196") (name "unconnected-(J2-Pad352)") (class "Default")
      (node (ref "J2") (pin "352") (pinfunction "352_352") (pintype "passive+no_connect"))
    )
    (net (code "197") (name "unconnected-(J2-Pad353)") (class "Default")
      (node (ref "J2") (pin "353") (pinfunction "353_353") (pintype "passive+no_connect"))
    )
    (net (code "198") (name "unconnected-(J2-Pad355)") (class "Default")
      (node (ref "J2") (pin "355") (pinfunction "355_355") (pintype "passive+no_connect"))
    )
    (net (code "199") (name "unconnected-(J2-Pad356)") (class "Default")
      (node (ref "J2") (pin "356") (pinfunction "356_356") (pintype "passive+no_connect"))
    )
    (net (code "200") (name "unconnected-(J2-Pad358)") (class "Default")
      (node (ref "J2") (pin "358") (pinfunction "358_358") (pintype "passive+no_connect"))
    )
    (net (code "201") (name "unconnected-(J2-Pad359)") (class "Default")
      (node (ref "J2") (pin "359") (pinfunction "359_359") (pintype "passive+no_connect"))
    )
    (net (code "202") (name "unconnected-(J2-Pad362)") (class "Default")
      (node (ref "J2") (pin "362") (pinfunction "362_362") (pintype "passive+no_connect"))
    )
    (net (code "203") (name "unconnected-(J2-Pad363)") (class "Default")
      (node (ref "J2") (pin "363") (pinfunction "363_363") (pintype "passive+no_connect"))
    )
    (net (code "204") (name "unconnected-(J2-Pad365)") (class "Default")
      (node (ref "J2") (pin "365") (pinfunction "365_365") (pintype "passive+no_connect"))
    )
    (net (code "205") (name "unconnected-(J2-Pad366)") (class "Default")
      (node (ref "J2") (pin "366") (pinfunction "366_366") (pintype "passive+no_connect"))
    )
    (net (code "206") (name "unconnected-(J2-Pad368)") (class "Default")
      (node (ref "J2") (pin "368") (pinfunction "368_368") (pintype "passive+no_connect"))
    )
    (net (code "207") (name "unconnected-(J2-Pad369)") (class "Default")
      (node (ref "J2") (pin "369") (pinfunction "369_369") (pintype "passive+no_connect"))
    )
    (net (code "208") (name "unconnected-(J2-Pad372)") (class "Default")
      (node (ref "J2") (pin "372") (pinfunction "372_372") (pintype "passive+no_connect"))
    )
    (net (code "209") (name "unconnected-(J2-Pad373)") (class "Default")
      (node (ref "J2") (pin "373") (pinfunction "373_373") (pintype "passive+no_connect"))
    )
    (net (code "210") (name "unconnected-(J2-Pad375)") (class "Default")
      (node (ref "J2") (pin "375") (pinfunction "375_375") (pintype "passive+no_connect"))
    )
    (net (code "211") (name "unconnected-(J2-Pad376)") (class "Default")
      (node (ref "J2") (pin "376") (pinfunction "376_376") (pintype "passive+no_connect"))
    )
    (net (code "212") (name "unconnected-(J2-Pad378)") (class "Default")
      (node (ref "J2") (pin "378") (pinfunction "378_378") (pintype "passive+no_connect"))
    )
    (net (code "213") (name "unconnected-(J2-Pad379)") (class "Default")
      (node (ref "J2") (pin "379") (pinfunction "379_379") (pintype "passive+no_connect"))
    )
    (net (code "214") (name "unconnected-(J2-Pad382)") (class "Default")
      (node (ref "J2") (pin "382") (pinfunction "382_382") (pintype "passive+no_connect"))
    )
    (net (code "215") (name "unconnected-(J2-Pad383)") (class "Default")
      (node (ref "J2") (pin "383") (pinfunction "383_383") (pintype "passive+no_connect"))
    )
    (net (code "216") (name "unconnected-(J2-Pad385)") (class "Default")
      (node (ref "J2") (pin "385") (pinfunction "385_385") (pintype "passive+no_connect"))
    )
    (net (code "217") (name "unconnected-(J2-Pad386)") (class "Default")
      (node (ref "J2") (pin "386") (pinfunction "386_386") (pintype "passive+no_connect"))
    )
    (net (code "218") (name "unconnected-(J2-Pad388)") (class "Default")
      (node (ref "J2") (pin "388") (pinfunction "388_388") (pintype "passive+no_connect"))
    )
    (net (code "219") (name "unconnected-(J2-Pad389)") (class "Default")
      (node (ref "J2") (pin "389") (pinfunction "389_389") (pintype "passive+no_connect"))
    )
    (net (code "220") (name "unconnected-(J2-Pad392)") (class "Default")
      (node (ref "J2") (pin "392") (pinfunction "392_392") (pintype "passive+no_connect"))
    )
    (net (code "221") (name "unconnected-(J2-Pad393)") (class "Default")
      (node (ref "J2") (pin "393") (pinfunction "393_393") (pintype "passive+no_connect"))
    )
    (net (code "222") (name "unconnected-(J2-Pad395)") (class "Default")
      (node (ref "J2") (pin "395") (pinfunction "395_395") (pintype "passive+no_connect"))
    )
    (net (code "223") (name "unconnected-(J2-Pad396)") (class "Default")
      (node (ref "J2") (pin "396") (pinfunction "396_396") (pintype "passive+no_connect"))
    )
    (net (code "224") (name "unconnected-(J2-Pad398)") (class "Default")
      (node (ref "J2") (pin "398") (pinfunction "398_398") (pintype "passive+no_connect"))
    )
    (net (code "225") (name "unconnected-(J2-Pad399)") (class "Default")
      (node (ref "J2") (pin "399") (pinfunction "399_399") (pintype "passive+no_connect"))
    )
  )
)
